# BSPD.net
KiCad netlist of a schematic drawn in Altium Designer
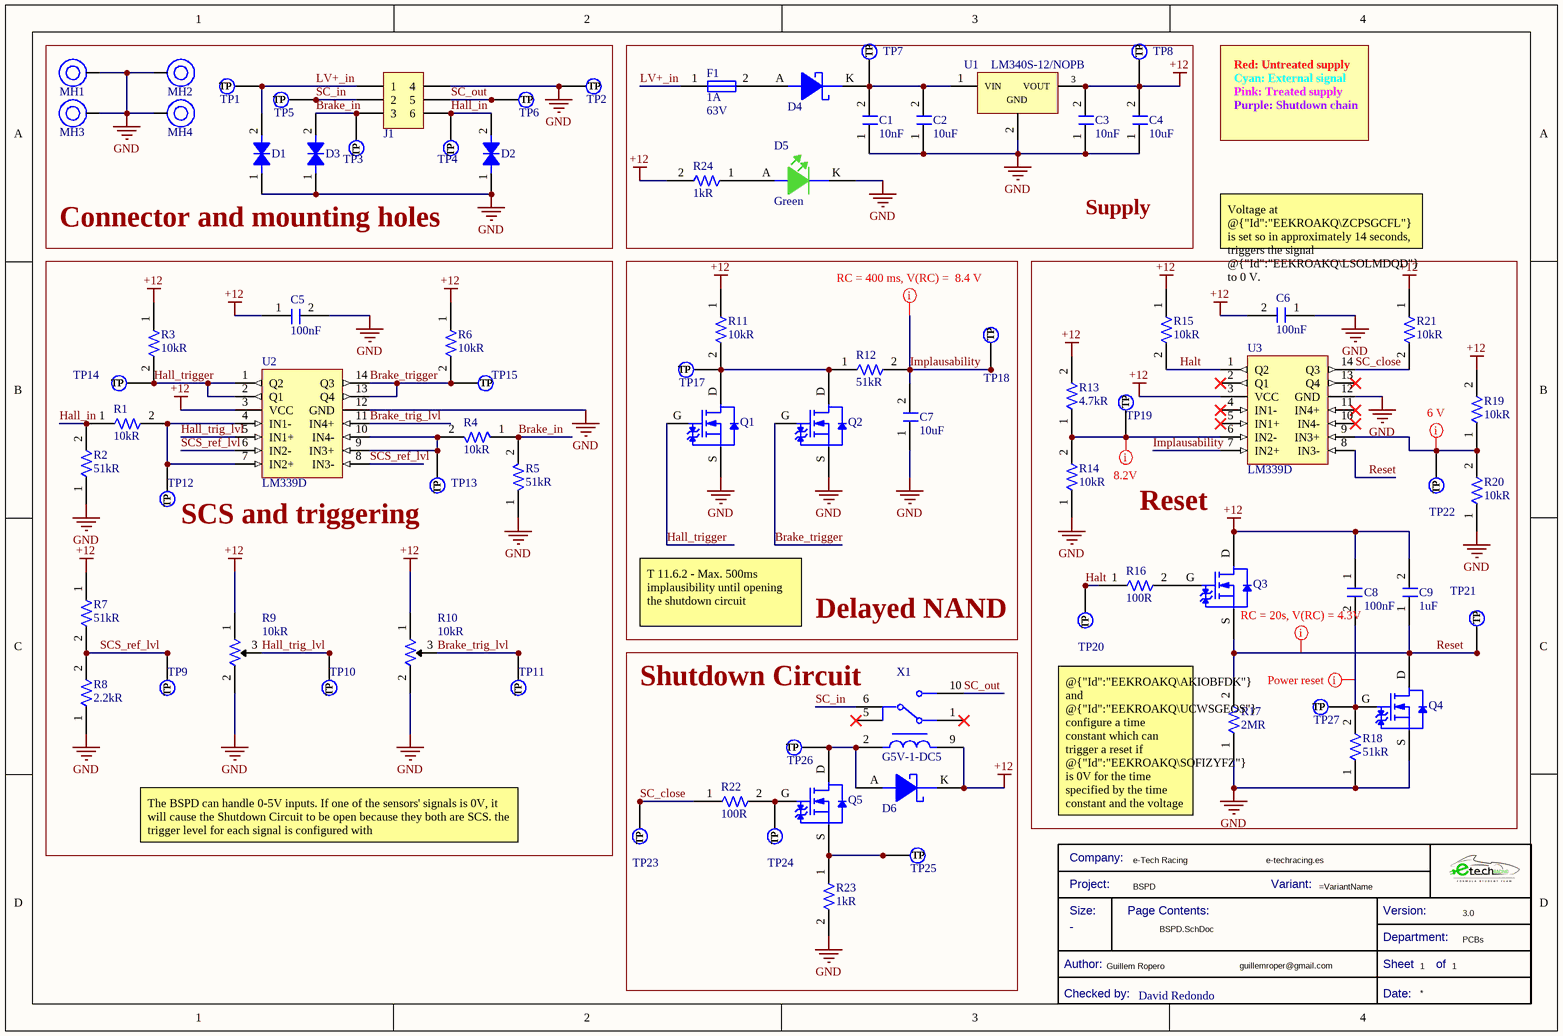
[diagram p0: BSPD.SchDoc]

(export (version "E")
  (design (tool "Eeschema 10.0.6"))
  (components
    (comp (ref "*")
      (value "Title Block_template")
      (description "Standard Title Block")
      (fields
        (field (name "SIZE") "-")
        (field (name ".CREATOR") "GP")
        (field (name ".PCBCHECK") "GP")
        (field (name ".SCHCHECK") "GP")
      )
      (libsource (lib "e-Tech_Racing") (part "Title Block_template"))
    )
    (comp (ref "C1")
      (value "885012008055")
      (footprint "C1206FNPC-RW")
      (description "Cap Cer 10000PF 50V C0G/NP0 1206")
      (fields
        (field (name "MANUFACTURER") "Wurth Electronics")
        (field (name "TOLERANCE") "5%")
        (field (name "CAPACITANCE") "10nF")
        (field (name ".CREATOR") "DO")
      )
      (libsource (lib "Passives") (part "C10n-50V-1206FNPC-C0G/NP0"))
    )
    (comp (ref "C2")
      (value "GRJ32ER71H106KE11L")
      (footprint "C10u-50V-1210FNPMLCC-X7R")
      (description "Multilayer Ceramic Capacitors MLCC - SMD/SMT 1210 10uF 50volts X7R +/-10% Soft Term")
      (fields
        (field (name "MANUFACTURER") "Murata")
        (field (name "TOLERANCE") "10%")
        (field (name "CAPACITANCE") "10uF")
        (field (name ".CREATOR") "DR")
      )
      (libsource (lib "Passives") (part "C10u-50V-1210FNPMLCC-X7R"))
    )
    (comp (ref "C3")
      (value "885012008055")
      (footprint "C1206FNPC-RW")
      (description "Cap Cer 10000PF 50V C0G/NP0 1206")
      (fields
        (field (name "MANUFACTURER") "Wurth Electronics")
        (field (name "TOLERANCE") "5%")
        (field (name "CAPACITANCE") "10nF")
        (field (name ".CREATOR") "DO")
      )
      (libsource (lib "Passives") (part "C10n-50V-1206FNPC-C0G/NP0"))
    )
    (comp (ref "C4")
      (value "GRJ32ER71H106KE11L")
      (footprint "C10u-50V-1210FNPMLCC-X7R")
      (description "Multilayer Ceramic Capacitors MLCC - SMD/SMT 1210 10uF 50volts X7R +/-10% Soft Term")
      (fields
        (field (name "MANUFACTURER") "Murata")
        (field (name "TOLERANCE") "10%")
        (field (name "CAPACITANCE") "10uF")
        (field (name ".CREATOR") "DR")
      )
      (libsource (lib "Passives") (part "C10u-50V-1210FNPMLCC-X7R"))
    )
    (comp (ref "C5")
      (value "885012208058")
      (footprint "C1206FNPC-RW")
      (description "Cap Cer 0.1UF 25V X7R 1206")
      (fields
        (field (name "MANUFACTURER") "Wurth Electronics")
        (field (name "TOLERANCE") "10%")
        (field (name "CAPACITANCE") "100nF")
        (field (name ".CREATOR") "DO")
      )
      (libsource (lib "Passives") (part "C100n-25V-1206FNPC-X7R"))
    )
    (comp (ref "C6")
      (value "885012208058")
      (footprint "C1206FNPC-RW")
      (description "Cap Cer 0.1UF 25V X7R 1206")
      (fields
        (field (name "MANUFACTURER") "Wurth Electronics")
        (field (name "TOLERANCE") "10%")
        (field (name "CAPACITANCE") "100nF")
        (field (name ".CREATOR") "DO")
      )
      (libsource (lib "Passives") (part "C100n-25V-1206FNPC-X7R"))
    )
    (comp (ref "C7")
      (value "885012208018")
      (footprint "C1206FNPC-RW")
      (description "Cap, 10ΜF, 10V, 10%, X7R, 1206")
      (fields
        (field (name "TOLERANCE") "10%")
        (field (name "CAPACITANCE") "10uF")
        (field (name ".CREATOR") "GP")
      )
      (libsource (lib "Passives") (part "C10u-10V-1206FNPC-X7R"))
    )
    (comp (ref "C8")
      (value "885012208058")
      (footprint "C1206FNPC-RW")
      (description "Cap Cer 0.1UF 25V X7R 1206")
      (fields
        (field (name "MANUFACTURER") "Wurth Electronics")
        (field (name "TOLERANCE") "10%")
        (field (name "CAPACITANCE") "100nF")
        (field (name ".CREATOR") "DO")
      )
      (libsource (lib "Passives") (part "C100n-25V-1206FNPC-X7R"))
    )
    (comp (ref "C9")
      (value "885012208036")
      (footprint "C1206FNPC-RW")
      (description "Cap Cer 1UF 16V X7R 1206")
      (fields
        (field (name "MANUFACTURER") "Wurth Electronics")
        (field (name "TOLERANCE") "10%")
        (field (name "CAPACITANCE") "1uF")
        (field (name ".CREATOR") "GP")
      )
      (libsource (lib "Passives") (part "C1u-16V-1206FNPC-X7R"))
    )
    (comp (ref "D1")
      (value "824551301")
      (footprint "DTVS-DO-214AB")
      (description "TVS diode [Würth Elektronik] 824551301 TVS diode")
      (fields (field (name "MANUFACTURER") "Wurth Electronics") (field (name ".CREATOR") "DO"))
      (libsource (lib "Filter components") (part "DTVS-40V-DO-214AB"))
    )
    (comp (ref "D2")
      (value "824501600")
      (footprint "DTVS-DO-214AC")
      (description "TVS diode [Würth Elektronik] 824501600 TVS diode")
      (fields (field (name "MANUFACTURER") "Wurth Electronics") (field (name ".CREATOR") "DO"))
      (libsource (lib "Filter components") (part "DTVS-6V-DO-214AC"))
    )
    (comp (ref "D3")
      (value "824501600")
      (footprint "DTVS-DO-214AC")
      (description "TVS diode [Würth Elektronik] 824501600 TVS diode")
      (fields (field (name "MANUFACTURER") "Wurth Electronics") (field (name ".CREATOR") "DO"))
      (libsource (lib "Filter components") (part "DTVS-6V-DO-214AC"))
    )
    (comp (ref "D4")
      (value "MBR0530")
      (footprint "DSC-SOD123")
      (description "VR=30V IF=500mA 30pF P=410mW")
      (fields (field (name ".CREATOR") "GP"))
      (libsource (lib "Filter components") (part "DSC-0.5/30-SOD123"))
    )
    (comp (ref "D5")
      (value "150080VS75000")
      (footprint "LED_0805_WE")
      (description "Led, Green, 570 Nm, 2 V, 30 Ma, 40 Mcd Rohs Compliant: Yes")
      (fields (field (name "COLOR") "Green") (field (name ".CREATOR") "DR"))
      (libsource (lib "Semiconductor") (part "LEDVS-0805-40"))
    )
    (comp (ref "D6")
      (value "MBR0530")
      (footprint "DSC-SOD123")
      (description "VR=30V IF=500mA 30pF P=410mW")
      (fields (field (name ".CREATOR") "GP"))
      (libsource (lib "Filter components") (part "DSC-0.5/30-SOD123"))
    )
    (comp (ref "F1")
      (value "0437001.WRA")
      (footprint "Fuse_1206")
      (description "Fuse Chip Fast Acting 1A 63V SMD Solder Pad 1206 Ceramic T/R Automotive")
      (fields
        (field (name "MANUFACTURER") "Littelfuse")
        (field (name "CURRENT RATING") "1A")
        (field (name "VOLTAGE RATING (DC)") "63V")
        (field (name ".CREATOR") "DO")
      )
      (libsource (lib "Filter components") (part "Fuse_1A_63V_1206"))
    )
    (comp (ref "J1")
      (value "J_NanoFit_2x3")
      (footprint "J_NanoFit_2x3")
      (libsource (lib "Electromechanical") (part "J_NanoFit_2x3"))
    )
    (comp (ref "MH1")
      (value "Mounting_Hole_M3")
      (footprint "Mounting_Hole_M3")
      (libsource (lib "Electromechanical") (part "Mounting_Hole_M3"))
    )
    (comp (ref "MH2")
      (value "Mounting_Hole_M3")
      (footprint "Mounting_Hole_M3")
      (libsource (lib "Electromechanical") (part "Mounting_Hole_M3"))
    )
    (comp (ref "MH3")
      (value "Mounting_Hole_M3")
      (footprint "Mounting_Hole_M3")
      (libsource (lib "Electromechanical") (part "Mounting_Hole_M3"))
    )
    (comp (ref "MH4")
      (value "Mounting_Hole_M3")
      (footprint "Mounting_Hole_M3")
      (libsource (lib "Electromechanical") (part "Mounting_Hole_M3"))
    )
    (comp (ref "Q1")
      (value "CPH3455-TL-H")
      (footprint "TRT-NCH-3/35-CPH")
      (description "CPH3455-TL-H N-channel MOSFET Transistor; 3 A; 35 V; 3-Pin CPH")
      (fields (field (name "MANUFACTURER") "ON Semiconductor") (field (name ".CREATOR") "GP"))
      (libsource (lib "Semiconductor") (part "TRT-NCH-3/35-CPH"))
    )
    (comp (ref "Q2")
      (value "CPH3455-TL-H")
      (footprint "TRT-NCH-3/35-CPH")
      (description "CPH3455-TL-H N-channel MOSFET Transistor; 3 A; 35 V; 3-Pin CPH")
      (fields (field (name "MANUFACTURER") "ON Semiconductor") (field (name ".CREATOR") "GP"))
      (libsource (lib "Semiconductor") (part "TRT-NCH-3/35-CPH"))
    )
    (comp (ref "Q3")
      (value "CPH3455-TL-H")
      (footprint "TRT-NCH-3/35-CPH")
      (description "CPH3455-TL-H N-channel MOSFET Transistor; 3 A; 35 V; 3-Pin CPH")
      (fields (field (name "MANUFACTURER") "ON Semiconductor") (field (name ".CREATOR") "GP"))
      (libsource (lib "Semiconductor") (part "TRT-NCH-3/35-CPH"))
    )
    (comp (ref "Q4")
      (value "CPH3455-TL-H")
      (footprint "TRT-NCH-3/35-CPH")
      (description "CPH3455-TL-H N-channel MOSFET Transistor; 3 A; 35 V; 3-Pin CPH")
      (fields (field (name "MANUFACTURER") "ON Semiconductor") (field (name ".CREATOR") "GP"))
      (libsource (lib "Semiconductor") (part "TRT-NCH-3/35-CPH"))
    )
    (comp (ref "Q5")
      (value "CPH3455-TL-H")
      (footprint "TRT-NCH-3/35-CPH")
      (description "CPH3455-TL-H N-channel MOSFET Transistor; 3 A; 35 V; 3-Pin CPH")
      (fields (field (name "MANUFACTURER") "ON Semiconductor") (field (name ".CREATOR") "GP"))
      (libsource (lib "Semiconductor") (part "TRT-NCH-3/35-CPH"))
    )
    (comp (ref "R1")
      (value "CRCW120610K0FKEA")
      (footprint "R1206FTK-W")
      (description "Res Thick Film 1206 10K Ohm 1% 0.25W(1/4W) +/-100ppm/ßC Pad SMD Automotive T/R")
      (fields (field (name "RESISTANCE") "10kR") (field (name ".CREATOR") "GP"))
      (libsource (lib "Passives") (part "R10k-1206FTK"))
    )
    (comp (ref "R2")
      (value "CRCW120610K0FKEA")
      (footprint "R1206FTK-W")
      (description "Res Thick Film 1206 51K Ohm 1% 1/4W ±100ppm/°C Molded SMD SMD Punched Carrier T/R")
      (fields
        (field (name "MANUFACTURER") "Panasonic")
        (field (name "MANUFACTURER PART NUMBER") "ERJ-S08F5102V")
        (field (name "RESISTANCE") "51kR")
        (field (name ".CREATOR") "DO")
      )
      (libsource (lib "Passives") (part "R51k-1206FTK"))
    )
    (comp (ref "R3")
      (value "CRCW120610K0FKEA")
      (footprint "R1206FTK-W")
      (description "Res Thick Film 1206 10K Ohm 1% 0.25W(1/4W) +/-100ppm/ßC Pad SMD Automotive T/R")
      (fields (field (name "RESISTANCE") "10kR") (field (name ".CREATOR") "GP"))
      (libsource (lib "Passives") (part "R10k-1206FTK"))
    )
    (comp (ref "R4")
      (value "CRCW120610K0FKEA")
      (footprint "R1206FTK-W")
      (description "Res Thick Film 1206 10K Ohm 1% 0.25W(1/4W) +/-100ppm/ßC Pad SMD Automotive T/R")
      (fields (field (name "RESISTANCE") "10kR") (field (name ".CREATOR") "GP"))
      (libsource (lib "Passives") (part "R10k-1206FTK"))
    )
    (comp (ref "R5")
      (value "CRCW120610K0FKEA")
      (footprint "R1206FTK-W")
      (description "Res Thick Film 1206 51K Ohm 1% 1/4W ±100ppm/°C Molded SMD SMD Punched Carrier T/R")
      (fields
        (field (name "MANUFACTURER") "Panasonic")
        (field (name "MANUFACTURER PART NUMBER") "ERJ-S08F5102V")
        (field (name "RESISTANCE") "51kR")
        (field (name ".CREATOR") "DO")
      )
      (libsource (lib "Passives") (part "R51k-1206FTK"))
    )
    (comp (ref "R6")
      (value "CRCW120610K0FKEA")
      (footprint "R1206FTK-W")
      (description "Res Thick Film 1206 10K Ohm 1% 0.25W(1/4W) +/-100ppm/ßC Pad SMD Automotive T/R")
      (fields (field (name "RESISTANCE") "10kR") (field (name ".CREATOR") "GP"))
      (libsource (lib "Passives") (part "R10k-1206FTK"))
    )
    (comp (ref "R7")
      (value "CRCW120610K0FKEA")
      (footprint "R1206FTK-W")
      (description "Res Thick Film 1206 51K Ohm 1% 1/4W ±100ppm/°C Molded SMD SMD Punched Carrier T/R")
      (fields
        (field (name "MANUFACTURER") "Panasonic")
        (field (name "MANUFACTURER PART NUMBER") "ERJ-S08F5102V")
        (field (name "RESISTANCE") "51kR")
        (field (name ".CREATOR") "DO")
      )
      (libsource (lib "Passives") (part "R51k-1206FTK"))
    )
    (comp (ref "R8")
      (value "CR1206-FX-2201ELF")
      (footprint "R1206FTK-W")
      (description "Res Thick Film 1206 2.2K Ohm 1% 1/4W ±100ppm/°C Molded SMD SMD Paper Tape on Plastic Reel")
      (fields
        (field (name "TOLERANCE") "1%")
        (field (name "RESISTANCE") "2.2kR")
        (field (name ".CREATOR") "AC")
      )
      (libsource (lib "Passives") (part "R2.2K-1206FTK"))
    )
    (comp (ref "R9")
      (value "3296W-1-103LF")
      (footprint "R10k-VTR")
      (description "Trimmer, Cermet, Rest 10 Kilohms, PCB, 25 Turns, Pwr-Rtg 0.5W, 3296 Series")
      (fields
        (field (name "MANUFACTURER") "Bourns")
        (field (name "TOLERANCE") "10%")
        (field (name "RESISTANCE") "10kR")
        (field (name ".CREATOR") "DO")
      )
      (libsource (lib "Passives") (part "R10k-VTR"))
    )
    (comp (ref "R10")
      (value "3296W-1-103LF")
      (footprint "R10k-VTR")
      (description "Trimmer, Cermet, Rest 10 Kilohms, PCB, 25 Turns, Pwr-Rtg 0.5W, 3296 Series")
      (fields
        (field (name "MANUFACTURER") "Bourns")
        (field (name "TOLERANCE") "10%")
        (field (name "RESISTANCE") "10kR")
        (field (name ".CREATOR") "DO")
      )
      (libsource (lib "Passives") (part "R10k-VTR"))
    )
    (comp (ref "R11")
      (value "CRCW120610K0FKEA")
      (footprint "R1206FTK-W")
      (description "Res Thick Film 1206 10K Ohm 1% 0.25W(1/4W) +/-100ppm/ßC Pad SMD Automotive T/R")
      (fields (field (name "RESISTANCE") "10kR") (field (name ".CREATOR") "GP"))
      (libsource (lib "Passives") (part "R10k-1206FTK"))
    )
    (comp (ref "R12")
      (value "CRCW120610K0FKEA")
      (footprint "R1206FTK-W")
      (description "Res Thick Film 1206 51K Ohm 1% 1/4W ±100ppm/°C Molded SMD SMD Punched Carrier T/R")
      (fields
        (field (name "MANUFACTURER") "Panasonic")
        (field (name "MANUFACTURER PART NUMBER") "ERJ-S08F5102V")
        (field (name "RESISTANCE") "51kR")
        (field (name ".CREATOR") "DO")
      )
      (libsource (lib "Passives") (part "R51k-1206FTK"))
    )
    (comp (ref "R13")
      (value "CRS1206-FX-4701ELF")
      (footprint "R1206FTK-W")
      (description "Res Thick Film 1206 4.7K Ohm 1% 1/2W ±100ppm/°C Molded SMD T/R")
      (fields
        (field (name "TOLERANCE") "1%")
        (field (name "RESISTANCE") "4.7kR")
        (field (name ".CREATOR") "AC")
      )
      (libsource (lib "Passives") (part "R4.7K-1206FTK"))
    )
    (comp (ref "R14")
      (value "CRCW120610K0FKEA")
      (footprint "R1206FTK-W")
      (description "Res Thick Film 1206 10K Ohm 1% 0.25W(1/4W) +/-100ppm/ßC Pad SMD Automotive T/R")
      (fields (field (name "RESISTANCE") "10kR") (field (name ".CREATOR") "GP"))
      (libsource (lib "Passives") (part "R10k-1206FTK"))
    )
    (comp (ref "R15")
      (value "CRCW120610K0FKEA")
      (footprint "R1206FTK-W")
      (description "Res Thick Film 1206 10K Ohm 1% 0.25W(1/4W) +/-100ppm/ßC Pad SMD Automotive T/R")
      (fields (field (name "RESISTANCE") "10kR") (field (name ".CREATOR") "GP"))
      (libsource (lib "Passives") (part "R10k-1206FTK"))
    )
    (comp (ref "R16")
      (value "CRG1206F100R")
      (footprint "R1206FTK-W")
      (description "Res Thick Film 1206 100 Ohm 1% 0.25W(1/4W) ±200ppm/C Pad SMD T/R")
      (fields
        (field (name "MANUFACTURER") "TE Connectivity")
        (field (name "TOLERANCE") "1%")
        (field (name "RESISTANCE") "100R")
        (field (name ".CREATOR") "AC")
      )
      (libsource (lib "Passives") (part "R100-1206FTK"))
    )
    (comp (ref "R17")
      (value "HVC1206-2M0FT3")
      (footprint "R1206FTK-W")
      (description "Res Thick Film 1206 2M Ohm 1% 0.3W ±100ppm/C Pad SMD T/R")
      (fields
        (field (name "MANUFACTURER") "TT Welwyn")
        (field (name "TOLERANCE") "1%")
        (field (name "RESISTENCE") "2MR")
        (field (name ".CREATOR") "DO")
      )
      (libsource (lib "Passives") (part "R2M-1206FTK"))
    )
    (comp (ref "R18")
      (value "CRCW120610K0FKEA")
      (footprint "R1206FTK-W")
      (description "Res Thick Film 1206 51K Ohm 1% 1/4W ±100ppm/°C Molded SMD SMD Punched Carrier T/R")
      (fields
        (field (name "MANUFACTURER") "Panasonic")
        (field (name "MANUFACTURER PART NUMBER") "ERJ-S08F5102V")
        (field (name "RESISTANCE") "51kR")
        (field (name ".CREATOR") "DO")
      )
      (libsource (lib "Passives") (part "R51k-1206FTK"))
    )
    (comp (ref "R19")
      (value "CRCW120610K0FKEA")
      (footprint "R1206FTK-W")
      (description "Res Thick Film 1206 10K Ohm 1% 0.25W(1/4W) +/-100ppm/ßC Pad SMD Automotive T/R")
      (fields (field (name "RESISTANCE") "10kR") (field (name ".CREATOR") "GP"))
      (libsource (lib "Passives") (part "R10k-1206FTK"))
    )
    (comp (ref "R20")
      (value "CRCW120610K0FKEA")
      (footprint "R1206FTK-W")
      (description "Res Thick Film 1206 10K Ohm 1% 0.25W(1/4W) +/-100ppm/ßC Pad SMD Automotive T/R")
      (fields (field (name "RESISTANCE") "10kR") (field (name ".CREATOR") "GP"))
      (libsource (lib "Passives") (part "R10k-1206FTK"))
    )
    (comp (ref "R21")
      (value "CRCW120610K0FKEA")
      (footprint "R1206FTK-W")
      (description "Res Thick Film 1206 10K Ohm 1% 0.25W(1/4W) +/-100ppm/ßC Pad SMD Automotive T/R")
      (fields (field (name "RESISTANCE") "10kR") (field (name ".CREATOR") "GP"))
      (libsource (lib "Passives") (part "R10k-1206FTK"))
    )
    (comp (ref "R22")
      (value "CRG1206F100R")
      (footprint "R1206FTK-W")
      (description "Res Thick Film 1206 100 Ohm 1% 0.25W(1/4W) ±200ppm/C Pad SMD T/R")
      (fields
        (field (name "MANUFACTURER") "TE Connectivity")
        (field (name "TOLERANCE") "1%")
        (field (name "RESISTANCE") "100R")
        (field (name ".CREATOR") "AC")
      )
      (libsource (lib "Passives") (part "R100-1206FTK"))
    )
    (comp (ref "R23")
      (value "ERJT08J102V")
      (footprint "R1206FTK-W")
      (description "Res Thick Film 1206 1K Ohm 5% 0.33W(1/3W) ±200ppm/C Pad SMD Automotive T/R")
      (fields
        (field (name "MANUFACTURER") "Panasonic")
        (field (name "TOLERANCE") "5%")
        (field (name "RESISTANCE") "1kR")
        (field (name ".CREATOR") "GP")
      )
      (libsource (lib "Passives") (part "R1k-1206FTK"))
    )
    (comp (ref "R24")
      (value "CR0805-JW-102ELF")
      (footprint "R0805FTK")
      (description "Res Thick Film 0805 1K Ohm 5% 1/8W ±200ppm/°C Molded SMD SMD Paper Tape on Plastic Reel")
      (fields
        (field (name "TOLERANCE") "5%")
        (field (name "RESISTANCE") "1kR")
        (field (name ".CREATOR") "GP")
      )
      (libsource (lib "Passives") (part "R1k-0805FTK"))
    )
    (comp (ref "TP1")
      (value "TestPoint")
      (footprint "TestPoint")
      (description "Test Point 1x1 mm")
      (fields (field (name ".CREATOR") "GP") (field (name ".PCBCHECK") "GP") (field (name ".SCHCHECK") "GP"))
      (libsource (lib "e-Tech_Racing") (part "TestPoint"))
    )
    (comp (ref "TP2")
      (value "TestPoint")
      (footprint "TestPoint")
      (description "Test Point 1x1 mm")
      (fields (field (name ".CREATOR") "GP") (field (name ".PCBCHECK") "GP") (field (name ".SCHCHECK") "GP"))
      (libsource (lib "e-Tech_Racing") (part "TestPoint"))
    )
    (comp (ref "TP3")
      (value "TestPoint")
      (footprint "TestPoint")
      (description "Test Point 1x1 mm")
      (fields (field (name ".CREATOR") "GP") (field (name ".PCBCHECK") "GP") (field (name ".SCHCHECK") "GP"))
      (libsource (lib "e-Tech_Racing") (part "TestPoint"))
    )
    (comp (ref "TP4")
      (value "TestPoint")
      (footprint "TestPoint")
      (description "Test Point 1x1 mm")
      (fields (field (name ".CREATOR") "GP") (field (name ".PCBCHECK") "GP") (field (name ".SCHCHECK") "GP"))
      (libsource (lib "e-Tech_Racing") (part "TestPoint"))
    )
    (comp (ref "TP5")
      (value "TestPoint")
      (footprint "TestPoint")
      (description "Test Point 1x1 mm")
      (fields (field (name ".CREATOR") "GP") (field (name ".PCBCHECK") "GP") (field (name ".SCHCHECK") "GP"))
      (libsource (lib "e-Tech_Racing") (part "TestPoint"))
    )
    (comp (ref "TP6")
      (value "TestPoint")
      (footprint "TestPoint")
      (description "Test Point 1x1 mm")
      (fields (field (name ".CREATOR") "GP") (field (name ".PCBCHECK") "GP") (field (name ".SCHCHECK") "GP"))
      (libsource (lib "e-Tech_Racing") (part "TestPoint"))
    )
    (comp (ref "TP7")
      (value "TestPoint")
      (footprint "TestPoint")
      (description "Test Point 1x1 mm")
      (fields (field (name ".CREATOR") "GP") (field (name ".PCBCHECK") "GP") (field (name ".SCHCHECK") "GP"))
      (libsource (lib "e-Tech_Racing") (part "TestPoint"))
    )
    (comp (ref "TP8")
      (value "TestPoint")
      (footprint "TestPoint")
      (description "Test Point 1x1 mm")
      (fields (field (name ".CREATOR") "GP") (field (name ".PCBCHECK") "GP") (field (name ".SCHCHECK") "GP"))
      (libsource (lib "e-Tech_Racing") (part "TestPoint"))
    )
    (comp (ref "TP9")
      (value "TestPoint")
      (footprint "TestPoint")
      (description "Test Point 1x1 mm")
      (fields (field (name ".CREATOR") "GP") (field (name ".PCBCHECK") "GP") (field (name ".SCHCHECK") "GP"))
      (libsource (lib "e-Tech_Racing") (part "TestPoint"))
    )
    (comp (ref "TP10")
      (value "TestPoint")
      (footprint "TestPoint")
      (description "Test Point 1x1 mm")
      (fields (field (name ".CREATOR") "GP") (field (name ".PCBCHECK") "GP") (field (name ".SCHCHECK") "GP"))
      (libsource (lib "e-Tech_Racing") (part "TestPoint"))
    )
    (comp (ref "TP11")
      (value "TestPoint")
      (footprint "TestPoint")
      (description "Test Point 1x1 mm")
      (fields (field (name ".CREATOR") "GP") (field (name ".PCBCHECK") "GP") (field (name ".SCHCHECK") "GP"))
      (libsource (lib "e-Tech_Racing") (part "TestPoint"))
    )
    (comp (ref "TP12")
      (value "TestPoint")
      (footprint "TestPoint")
      (description "Test Point 1x1 mm")
      (fields (field (name ".CREATOR") "GP") (field (name ".PCBCHECK") "GP") (field (name ".SCHCHECK") "GP"))
      (libsource (lib "e-Tech_Racing") (part "TestPoint"))
    )
    (comp (ref "TP13")
      (value "TestPoint")
      (footprint "TestPoint")
      (description "Test Point 1x1 mm")
      (fields (field (name ".CREATOR") "GP") (field (name ".PCBCHECK") "GP") (field (name ".SCHCHECK") "GP"))
      (libsource (lib "e-Tech_Racing") (part "TestPoint"))
    )
    (comp (ref "TP14")
      (value "TestPoint")
      (footprint "TestPoint")
      (description "Test Point 1x1 mm")
      (fields (field (name ".CREATOR") "GP") (field (name ".PCBCHECK") "GP") (field (name ".SCHCHECK") "GP"))
      (libsource (lib "e-Tech_Racing") (part "TestPoint"))
    )
    (comp (ref "TP15")
      (value "TestPoint")
      (footprint "TestPoint")
      (description "Test Point 1x1 mm")
      (fields (field (name ".CREATOR") "GP") (field (name ".PCBCHECK") "GP") (field (name ".SCHCHECK") "GP"))
      (libsource (lib "e-Tech_Racing") (part "TestPoint"))
    )
    (comp (ref "TP17")
      (value "TestPoint")
      (footprint "TestPoint")
      (description "Test Point 1x1 mm")
      (fields (field (name ".CREATOR") "GP") (field (name ".PCBCHECK") "GP") (field (name ".SCHCHECK") "GP"))
      (libsource (lib "e-Tech_Racing") (part "TestPoint"))
    )
    (comp (ref "TP18")
      (value "TestPoint")
      (footprint "TestPoint")
      (description "Test Point 1x1 mm")
      (fields (field (name ".CREATOR") "GP") (field (name ".PCBCHECK") "GP") (field (name ".SCHCHECK") "GP"))
      (libsource (lib "e-Tech_Racing") (part "TestPoint"))
    )
    (comp (ref "TP19")
      (value "TestPoint")
      (footprint "TestPoint")
      (description "Test Point 1x1 mm")
      (fields (field (name ".CREATOR") "GP") (field (name ".PCBCHECK") "GP") (field (name ".SCHCHECK") "GP"))
      (libsource (lib "e-Tech_Racing") (part "TestPoint"))
    )
    (comp (ref "TP20")
      (value "TestPoint")
      (footprint "TestPoint")
      (description "Test Point 1x1 mm")
      (fields (field (name ".CREATOR") "GP") (field (name ".PCBCHECK") "GP") (field (name ".SCHCHECK") "GP"))
      (libsource (lib "e-Tech_Racing") (part "TestPoint"))
    )
    (comp (ref "TP21")
      (value "TestPoint")
      (footprint "TestPoint")
      (description "Test Point 1x1 mm")
      (fields (field (name ".CREATOR") "GP") (field (name ".PCBCHECK") "GP") (field (name ".SCHCHECK") "GP"))
      (libsource (lib "e-Tech_Racing") (part "TestPoint"))
    )
    (comp (ref "TP22")
      (value "TestPoint")
      (footprint "TestPoint")
      (description "Test Point 1x1 mm")
      (fields (field (name ".CREATOR") "GP") (field (name ".PCBCHECK") "GP") (field (name ".SCHCHECK") "GP"))
      (libsource (lib "e-Tech_Racing") (part "TestPoint"))
    )
    (comp (ref "TP23")
      (value "TestPoint")
      (footprint "TestPoint")
      (description "Test Point 1x1 mm")
      (fields (field (name ".CREATOR") "GP") (field (name ".PCBCHECK") "GP") (field (name ".SCHCHECK") "GP"))
      (libsource (lib "e-Tech_Racing") (part "TestPoint"))
    )
    (comp (ref "TP24")
      (value "TestPoint")
      (footprint "TestPoint")
      (description "Test Point 1x1 mm")
      (fields (field (name ".CREATOR") "GP") (field (name ".PCBCHECK") "GP") (field (name ".SCHCHECK") "GP"))
      (libsource (lib "e-Tech_Racing") (part "TestPoint"))
    )
    (comp (ref "TP25")
      (value "TestPoint")
      (footprint "TestPoint")
      (description "Test Point 1x1 mm")
      (fields (field (name ".CREATOR") "GP") (field (name ".PCBCHECK") "GP") (field (name ".SCHCHECK") "GP"))
      (libsource (lib "e-Tech_Racing") (part "TestPoint"))
    )
    (comp (ref "TP26")
      (value "TestPoint")
      (footprint "TestPoint")
      (description "Test Point 1x1 mm")
      (fields (field (name ".CREATOR") "GP") (field (name ".PCBCHECK") "GP") (field (name ".SCHCHECK") "GP"))
      (libsource (lib "e-Tech_Racing") (part "TestPoint"))
    )
    (comp (ref "TP27")
      (value "TestPoint")
      (footprint "TestPoint")
      (description "Test Point 1x1 mm")
      (fields (field (name ".CREATOR") "GP") (field (name ".PCBCHECK") "GP") (field (name ".SCHCHECK") "GP"))
      (libsource (lib "e-Tech_Racing") (part "TestPoint"))
    )
    (comp (ref "U1")
      (value "LM340S-12/NOPB")
      (footprint "LDO_35V-1/12V-TO220")
      (description "1.5-A, 35-V, linear voltage regulator 3-TO-220 -40 to 125")
      (fields
        (field (name "MANUFACTURER") "Texas Instruments")
        (field (name "VOLTAGE") "12V")
        (field (name "MANUFACTURER PART NUMBER") "LM340S-12/NOPB")
        (field (name ".CREATOR") "AC")
      )
      (libsource (lib "Semiconductor") (part "LDO_35V-1/12V-TO220"))
    )
    (comp (ref "U2")
      (value "LM339D")
      (footprint "Array_4_Amp_LM339D")
      (description "Comparator Quad ±18V/36V 14-Pin SOIC Tube")
      (fields
        (field (name "MANUFACTURER") "Texas Instruments")
        (field (name "MANUFACTURER PART NUMBER") "LM339D")
        (field (name ".CREATOR") "DO")
      )
      (libsource (lib "Integrated circuits") (part "Array_4_Comp_LM339D"))
    )
    (comp (ref "U3")
      (value "LM339D")
      (footprint "Array_4_Amp_LM339D")
      (description "Comparator Quad ±18V/36V 14-Pin SOIC Tube")
      (fields
        (field (name "MANUFACTURER") "Texas Instruments")
        (field (name "MANUFACTURER PART NUMBER") "LM339D")
        (field (name ".CREATOR") "DO")
      )
      (libsource (lib "Integrated circuits") (part "Array_4_Comp_LM339D"))
    )
    (comp (ref "X1")
      (value "G5V-1-DC5")
      (footprint "Relay_G5V-1-DC5")
      (description "Electromechanical Relay SPDT 1A 5VDC 167Ohm Through Hole")
      (fields
        (field (name "MANUFACTURER") "Omron")
        (field (name "SUPPLIER PART NUMBER 1") "G5V-1-DC5")
        (field (name ".CREATOR") "DO")
      )
      (libsource (lib "Electromechanical") (part "Relay_G5V-1-DC5"))
    )
  )
  (nets
    (net (code "1") (name "+12") (class "Default")
      (node (ref "C3") (pin "2") (pinfunction "2_2") (pintype "passive"))
      (node (ref "C4") (pin "2") (pinfunction "2_2") (pintype "passive"))
      (node (ref "C5") (pin "1") (pinfunction "1_1") (pintype "passive"))
      (node (ref "C6") (pin "2") (pinfunction "2_2") (pintype "passive"))
      (node (ref "C8") (pin "1") (pinfunction "1_1") (pintype "passive"))
      (node (ref "C9") (pin "2") (pinfunction "2_2") (pintype "passive"))
      (node (ref "D6") (pin "K") (pinfunction "K_K") (pintype "passive"))
      (node (ref "Q3") (pin "D") (pinfunction "D_D") (pintype "passive"))
      (node (ref "R10") (pin "1") (pinfunction "2_1") (pintype "passive"))
      (node (ref "R11") (pin "1") (pinfunction "1_1") (pintype "passive"))
      (node (ref "R13") (pin "2") (pinfunction "2_2") (pintype "passive"))
      (node (ref "R15") (pin "1") (pinfunction "1_1") (pintype "passive"))
      (node (ref "R19") (pin "2") (pinfunction "2_2") (pintype "passive"))
      (node (ref "R21") (pin "1") (pinfunction "1_1") (pintype "passive"))
      (node (ref "R24") (pin "2") (pinfunction "2_2") (pintype "passive"))
      (node (ref "R3") (pin "1") (pinfunction "1_1") (pintype "passive"))
      (node (ref "R6") (pin "1") (pinfunction "1_1") (pintype "passive"))
      (node (ref "R7") (pin "1") (pinfunction "1_1") (pintype "passive"))
      (node (ref "R9") (pin "1") (pinfunction "2_1") (pintype "passive"))
      (node (ref "TP8") (pin "1") (pinfunction "TP_1") (pintype "passive"))
      (node (ref "U1") (pin "3") (pinfunction "VOUT_3") (pintype "passive"))
      (node (ref "U2") (pin "3") (pinfunction "VCC_3") (pintype "power_in"))
      (node (ref "U3") (pin "3") (pinfunction "VCC_3") (pintype "power_in"))
      (node (ref "X1") (pin "9") (pinfunction "9_9") (pintype "passive"))
    )
    (net (code "2") (name "/Brake_in") (class "Default")
      (node (ref "D3") (pin "2") (pinfunction "2_2") (pintype "passive"))
      (node (ref "J1") (pin "3") (pinfunction "3_3") (pintype "passive"))
      (node (ref "R4") (pin "1") (pinfunction "1_1") (pintype "passive"))
      (node (ref "R5") (pin "2") (pinfunction "2_2") (pintype "passive"))
      (node (ref "TP3") (pin "1") (pinfunction "TP_1") (pintype "passive"))
    )
    (net (code "3") (name "/Brake_trig_lvl") (class "Default")
      (node (ref "R10") (pin "3") (pinfunction "3_3") (pintype "passive"))
      (node (ref "TP11") (pin "1") (pinfunction "TP_1") (pintype "passive"))
      (node (ref "U2") (pin "11") (pinfunction "IN4+_11") (pintype "input"))
    )
    (net (code "4") (name "/Brake_trigger") (class "Default")
      (node (ref "Q2") (pin "G") (pinfunction "G_G") (pintype "passive"))
      (node (ref "R6") (pin "2") (pinfunction "2_2") (pintype "passive"))
      (node (ref "TP15") (pin "1") (pinfunction "TP_1") (pintype "passive"))
      (node (ref "U2") (pin "13") (pinfunction "Q4_13") (pintype "output"))
      (node (ref "U2") (pin "14") (pinfunction "Q3_14") (pintype "output"))
    )
    (net (code "5") (name "/Hall_in") (class "Default")
      (node (ref "D2") (pin "2") (pinfunction "2_2") (pintype "passive"))
      (node (ref "J1") (pin "6") (pinfunction "6_6") (pintype "passive"))
      (node (ref "R1") (pin "1") (pinfunction "1_1") (pintype "passive"))
      (node (ref "R2") (pin "2") (pinfunction "2_2") (pintype "passive"))
      (node (ref "TP4") (pin "1") (pinfunction "TP_1") (pintype "passive"))
    )
    (net (code "6") (name "/Hall_trig_lvl") (class "Default")
      (node (ref "R9") (pin "3") (pinfunction "3_3") (pintype "passive"))
      (node (ref "TP10") (pin "1") (pinfunction "TP_1") (pintype "passive"))
      (node (ref "U2") (pin "5") (pinfunction "IN1+_5") (pintype "input"))
    )
    (net (code "7") (name "/Hall_trigger") (class "Default")
      (node (ref "Q1") (pin "G") (pinfunction "G_G") (pintype "passive"))
      (node (ref "R3") (pin "2") (pinfunction "2_2") (pintype "passive"))
      (node (ref "TP14") (pin "1") (pinfunction "TP_1") (pintype "passive"))
      (node (ref "U2") (pin "1") (pinfunction "Q2_1") (pintype "output"))
      (node (ref "U2") (pin "2") (pinfunction "Q1_2") (pintype "output"))
    )
    (net (code "8") (name "/Halt") (class "Default")
      (node (ref "R15") (pin "2") (pinfunction "2_2") (pintype "passive"))
      (node (ref "R16") (pin "1") (pinfunction "1_1") (pintype "passive"))
      (node (ref "TP20") (pin "1") (pinfunction "TP_1") (pintype "passive"))
      (node (ref "U3") (pin "1") (pinfunction "Q2_1") (pintype "output"))
    )
    (net (code "9") (name "/Implausability") (class "Default")
      (node (ref "C7") (pin "2") (pinfunction "2_2") (pintype "passive"))
      (node (ref "R12") (pin "2") (pinfunction "2_2") (pintype "passive"))
      (node (ref "TP18") (pin "1") (pinfunction "TP_1") (pintype "passive"))
      (node (ref "U3") (pin "7") (pinfunction "IN2+_7") (pintype "input"))
    )
    (net (code "10") (name "/LV+_in") (class "Default")
      (node (ref "D1") (pin "2") (pinfunction "2_2") (pintype "passive"))
      (node (ref "F1") (pin "1") (pinfunction "1_1") (pintype "passive"))
      (node (ref "J1") (pin "1") (pinfunction "1_1") (pintype "passive"))
      (node (ref "TP1") (pin "1") (pinfunction "TP_1") (pintype "passive"))
    )
    (net (code "11") (name "/Reset") (class "Default")
      (node (ref "C9") (pin "1") (pinfunction "1_1") (pintype "passive"))
      (node (ref "Q3") (pin "S") (pinfunction "S_S") (pintype "passive"))
      (node (ref "Q4") (pin "D") (pinfunction "D_D") (pintype "passive"))
      (node (ref "R17") (pin "2") (pinfunction "2_2") (pintype "passive"))
      (node (ref "TP21") (pin "1") (pinfunction "TP_1") (pintype "passive"))
      (node (ref "U3") (pin "8") (pinfunction "IN3-_8") (pintype "input"))
    )
    (net (code "12") (name "/SCS_ref_lvl") (class "Default")
      (node (ref "R7") (pin "2") (pinfunction "2_2") (pintype "passive"))
      (node (ref "R8") (pin "2") (pinfunction "2_2") (pintype "passive"))
      (node (ref "TP9") (pin "1") (pinfunction "TP_1") (pintype "passive"))
      (node (ref "U2") (pin "6") (pinfunction "IN2-_6") (pintype "input"))
      (node (ref "U2") (pin "8") (pinfunction "IN3-_8") (pintype "input"))
    )
    (net (code "13") (name "/SC_close") (class "Default")
      (node (ref "R21") (pin "2") (pinfunction "2_2") (pintype "passive"))
      (node (ref "R22") (pin "1") (pinfunction "1_1") (pintype "passive"))
      (node (ref "TP23") (pin "1") (pinfunction "TP_1") (pintype "passive"))
      (node (ref "U3") (pin "14") (pinfunction "Q3_14") (pintype "output"))
    )
    (net (code "14") (name "/SC_in") (class "Default")
      (node (ref "J1") (pin "2") (pinfunction "2_2") (pintype "passive"))
      (node (ref "TP5") (pin "1") (pinfunction "TP_1") (pintype "passive"))
      (node (ref "X1") (pin "6") (pinfunction "6_6") (pintype "passive"))
    )
    (net (code "15") (name "/SC_out") (class "Default")
      (node (ref "J1") (pin "5") (pinfunction "5_5") (pintype "passive"))
      (node (ref "TP6") (pin "1") (pinfunction "TP_1") (pintype "passive"))
      (node (ref "X1") (pin "10") (pinfunction "10_10") (pintype "passive"))
    )
    (net (code "16") (name "GND") (class "Default")
      (node (ref "C1") (pin "1") (pinfunction "1_1") (pintype "passive"))
      (node (ref "C2") (pin "1") (pinfunction "1_1") (pintype "passive"))
      (node (ref "C3") (pin "1") (pinfunction "1_1") (pintype "passive"))
      (node (ref "C4") (pin "1") (pinfunction "1_1") (pintype "passive"))
      (node (ref "C5") (pin "2") (pinfunction "2_2") (pintype "passive"))
      (node (ref "C6") (pin "1") (pinfunction "1_1") (pintype "passive"))
      (node (ref "C7") (pin "1") (pinfunction "1_1") (pintype "passive"))
      (node (ref "D1") (pin "1") (pinfunction "1_1") (pintype "passive"))
      (node (ref "D2") (pin "1") (pinfunction "1_1") (pintype "passive"))
      (node (ref "D3") (pin "1") (pinfunction "1_1") (pintype "passive"))
      (node (ref "D5") (pin "K") (pinfunction "K_K") (pintype "passive"))
      (node (ref "J1") (pin "4") (pinfunction "4_4") (pintype "passive"))
      (node (ref "MH1") (pin "1") (pinfunction "1_1") (pintype "passive"))
      (node (ref "MH2") (pin "1") (pinfunction "1_1") (pintype "passive"))
      (node (ref "MH3") (pin "1") (pinfunction "1_1") (pintype "passive"))
      (node (ref "MH4") (pin "1") (pinfunction "1_1") (pintype "passive"))
      (node (ref "Q1") (pin "S") (pinfunction "S_S") (pintype "passive"))
      (node (ref "Q2") (pin "S") (pinfunction "S_S") (pintype "passive"))
      (node (ref "Q4") (pin "S") (pinfunction "S_S") (pintype "passive"))
      (node (ref "R10") (pin "2") (pinfunction "2_2") (pintype "passive"))
      (node (ref "R14") (pin "1") (pinfunction "1_1") (pintype "passive"))
      (node (ref "R17") (pin "1") (pinfunction "1_1") (pintype "passive"))
      (node (ref "R18") (pin "1") (pinfunction "1_1") (pintype "passive"))
      (node (ref "R2") (pin "1") (pinfunction "1_1") (pintype "passive"))
      (node (ref "R20") (pin "1") (pinfunction "1_1") (pintype "passive"))
      (node (ref "R23") (pin "2") (pinfunction "2_2") (pintype "passive"))
      (node (ref "R5") (pin "1") (pinfunction "1_1") (pintype "passive"))
      (node (ref "R8") (pin "1") (pinfunction "1_1") (pintype "passive"))
      (node (ref "R9") (pin "2") (pinfunction "2_2") (pintype "passive"))
      (node (ref "TP2") (pin "1") (pinfunction "TP_1") (pintype "passive"))
      (node (ref "U1") (pin "2") (pinfunction "GND_2") (pintype "passive"))
      (node (ref "U2") (pin "12") (pinfunction "GND_12") (pintype "power_in"))
      (node (ref "U3") (pin "12") (pinfunction "GND_12") (pintype "power_in"))
    )
    (net (code "17") (name "Net-(D4-PadA)") (class "Default")
      (node (ref "D4") (pin "A") (pinfunction "A_A") (pintype "passive"))
      (node (ref "F1") (pin "2") (pinfunction "2_2") (pintype "passive"))
    )
    (net (code "18") (name "Net-(D5-PadA)") (class "Default")
      (node (ref "D5") (pin "A") (pinfunction "A_A") (pintype "passive"))
      (node (ref "R24") (pin "1") (pinfunction "1_1") (pintype "passive"))
    )
    (net (code "19") (name "Net-(Q3-PadG)") (class "Default")
      (node (ref "Q3") (pin "G") (pinfunction "G_G") (pintype "passive"))
      (node (ref "R16") (pin "2") (pinfunction "2_2") (pintype "passive"))
    )
    (net (code "20") (name "Net-(TP7-TP)") (class "Default")
      (node (ref "C1") (pin "2") (pinfunction "2_2") (pintype "passive"))
      (node (ref "C2") (pin "2") (pinfunction "2_2") (pintype "passive"))
      (node (ref "D4") (pin "K") (pinfunction "K_K") (pintype "passive"))
      (node (ref "TP7") (pin "1") (pinfunction "TP_1") (pintype "passive"))
      (node (ref "U1") (pin "1") (pinfunction "VIN_1") (pintype "passive"))
    )
    (net (code "21") (name "Net-(TP12-TP)") (class "Default")
      (node (ref "R1") (pin "2") (pinfunction "2_2") (pintype "passive"))
      (node (ref "TP12") (pin "1") (pinfunction "TP_1") (pintype "passive"))
      (node (ref "U2") (pin "4") (pinfunction "IN1-_4") (pintype "input"))
      (node (ref "U2") (pin "7") (pinfunction "IN2+_7") (pintype "input"))
    )
    (net (code "22") (name "Net-(TP13-TP)") (class "Default")
      (node (ref "R4") (pin "2") (pinfunction "2_2") (pintype "passive"))
      (node (ref "TP13") (pin "1") (pinfunction "TP_1") (pintype "passive"))
      (node (ref "U2") (pin "10") (pinfunction "IN4-_10") (pintype "input"))
      (node (ref "U2") (pin "9") (pinfunction "IN3+_9") (pintype "input"))
    )
    (net (code "23") (name "Net-(TP17-TP)") (class "Default")
      (node (ref "Q1") (pin "D") (pinfunction "D_D") (pintype "passive"))
      (node (ref "Q2") (pin "D") (pinfunction "D_D") (pintype "passive"))
      (node (ref "R11") (pin "2") (pinfunction "2_2") (pintype "passive"))
      (node (ref "R12") (pin "1") (pinfunction "1_1") (pintype "passive"))
      (node (ref "TP17") (pin "1") (pinfunction "TP_1") (pintype "passive"))
    )
    (net (code "24") (name "Net-(TP19-TP)") (class "Default")
      (node (ref "R13") (pin "1") (pinfunction "1_1") (pintype "passive"))
      (node (ref "R14") (pin "2") (pinfunction "2_2") (pintype "passive"))
      (node (ref "TP19") (pin "1") (pinfunction "TP_1") (pintype "passive"))
      (node (ref "U3") (pin "6") (pinfunction "IN2-_6") (pintype "input"))
    )
    (net (code "25") (name "Net-(TP22-TP)") (class "Default")
      (node (ref "R19") (pin "1") (pinfunction "1_1") (pintype "passive"))
      (node (ref "R20") (pin "2") (pinfunction "2_2") (pintype "passive"))
      (node (ref "TP22") (pin "1") (pinfunction "TP_1") (pintype "passive"))
      (node (ref "U3") (pin "9") (pinfunction "IN3+_9") (pintype "input"))
    )
    (net (code "26") (name "Net-(TP24-TP)") (class "Default")
      (node (ref "Q5") (pin "G") (pinfunction "G_G") (pintype "passive"))
      (node (ref "R22") (pin "2") (pinfunction "2_2") (pintype "passive"))
      (node (ref "TP24") (pin "1") (pinfunction "TP_1") (pintype "passive"))
    )
    (net (code "27") (name "Net-(TP25-TP)") (class "Default")
      (node (ref "Q5") (pin "S") (pinfunction "S_S") (pintype "passive"))
      (node (ref "R23") (pin "1") (pinfunction "1_1") (pintype "passive"))
      (node (ref "TP25") (pin "1") (pinfunction "TP_1") (pintype "passive"))
    )
    (net (code "28") (name "Net-(TP26-TP)") (class "Default")
      (node (ref "D6") (pin "A") (pinfunction "A_A") (pintype "passive"))
      (node (ref "Q5") (pin "D") (pinfunction "D_D") (pintype "passive"))
      (node (ref "TP26") (pin "1") (pinfunction "TP_1") (pintype "passive"))
      (node (ref "X1") (pin "2") (pinfunction "2_2") (pintype "passive"))
    )
    (net (code "29") (name "Net-(TP27-TP)") (class "Default")
      (node (ref "C8") (pin "2") (pinfunction "2_2") (pintype "passive"))
      (node (ref "Q4") (pin "G") (pinfunction "G_G") (pintype "passive"))
      (node (ref "R18") (pin "2") (pinfunction "2_2") (pintype "passive"))
      (node (ref "TP27") (pin "1") (pinfunction "TP_1") (pintype "passive"))
    )
    (net (code "30") (name "unconnected-(U3-IN1+-Pad5)") (class "Default")
      (node (ref "U3") (pin "5") (pinfunction "IN1+_5") (pintype "input+no_connect"))
    )
    (net (code "31") (name "unconnected-(U3-IN1--Pad4)") (class "Default")
      (node (ref "U3") (pin "4") (pinfunction "IN1-_4") (pintype "input+no_connect"))
    )
    (net (code "32") (name "unconnected-(U3-IN4+-Pad11)") (class "Default")
      (node (ref "U3") (pin "11") (pinfunction "IN4+_11") (pintype "input+no_connect"))
    )
    (net (code "33") (name "unconnected-(U3-IN4--Pad10)") (class "Default")
      (node (ref "U3") (pin "10") (pinfunction "IN4-_10") (pintype "input+no_connect"))
    )
    (net (code "34") (name "unconnected-(U3-Q1-Pad2)") (class "Default")
      (node (ref "U3") (pin "2") (pinfunction "Q1_2") (pintype "output+no_connect"))
    )
    (net (code "35") (name "unconnected-(U3-Q4-Pad13)") (class "Default")
      (node (ref "U3") (pin "13") (pinfunction "Q4_13") (pintype "output+no_connect"))
    )
    (net (code "36") (name "unconnected-(X1-Pad1)") (class "Default")
      (node (ref "X1") (pin "1") (pinfunction "1_1") (pintype "passive+no_connect"))
    )
    (net (code "37") (name "unconnected-(X1-Pad5)") (class "Default")
      (node (ref "X1") (pin "5") (pinfunction "5_5") (pintype "passive+no_connect"))
    )
  )
)
